# output.net
KiCad netlist of a schematic drawn in Altium Designer
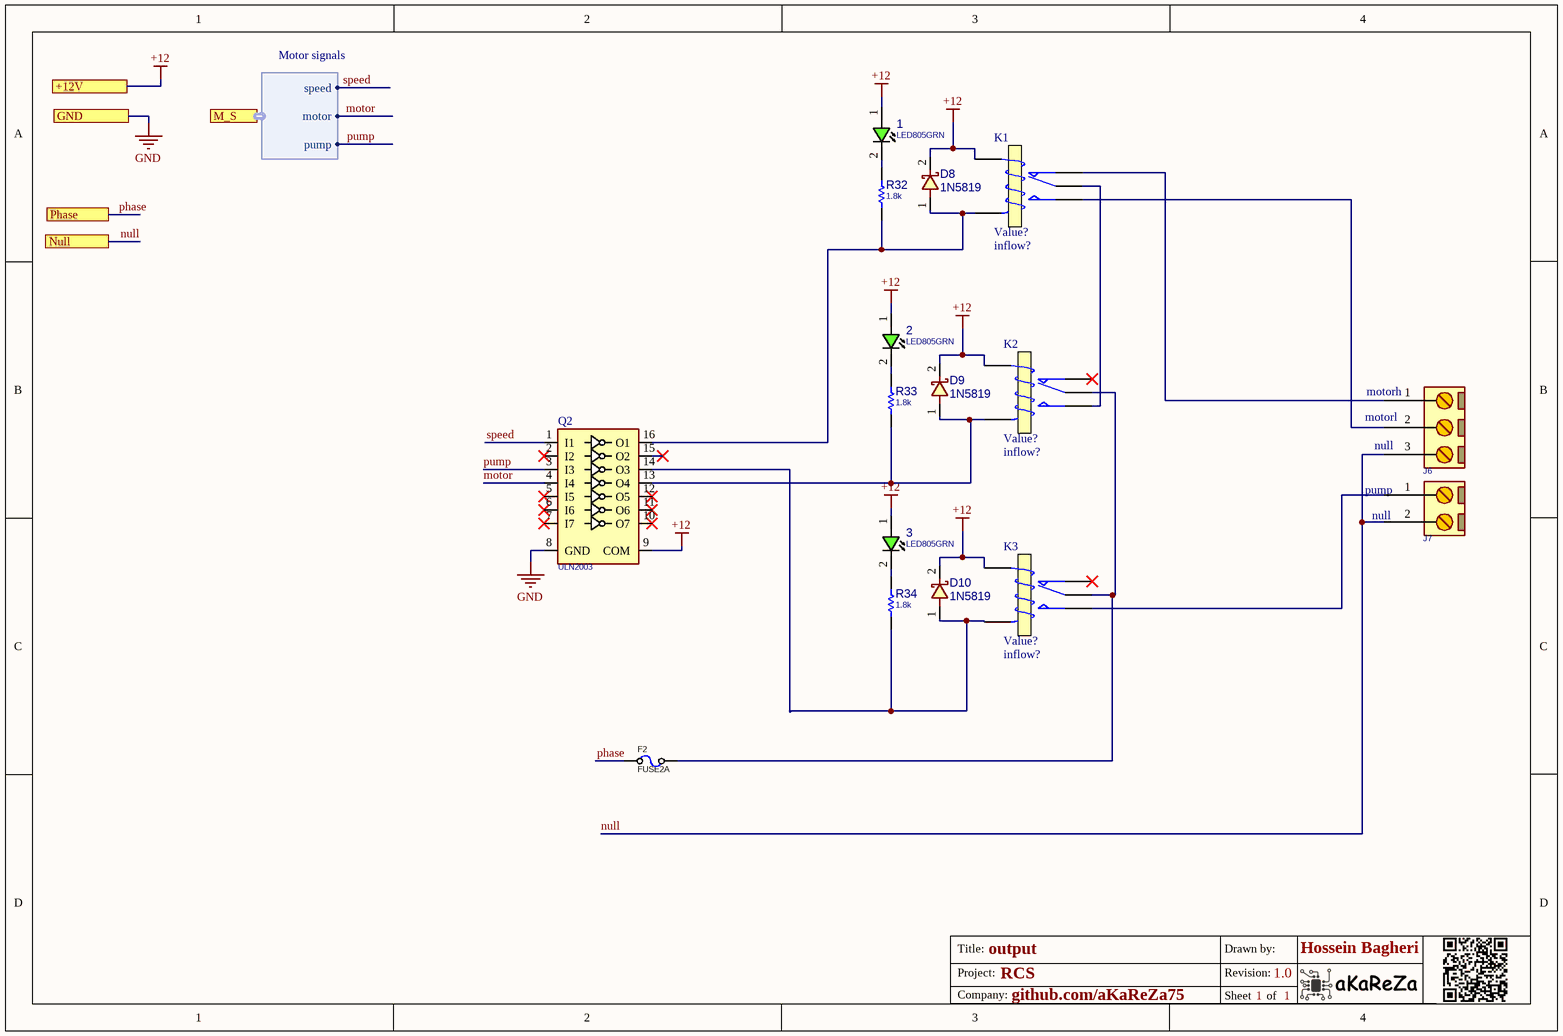
[diagram p0: output.SchDoc]

(export (version "E")
  (design (tool "Eeschema 10.0.6"))
  (components
    (comp (ref "1")
      (value "LED805GRN")
      (footprint "LED0805GRN")
      (description "LED, SMD, 0805, GREEN")
      (libsource (lib "Chila_PCB") (part "LED_SMD_0805_GRN"))
    )
    (comp (ref "2")
      (value "LED805GRN")
      (footprint "LED0805GRN")
      (description "LED, SMD, 0805, GREEN")
      (libsource (lib "Chila_PCB") (part "LED_SMD_0805_GRN"))
    )
    (comp (ref "3")
      (value "LED805GRN")
      (footprint "LED0805GRN")
      (description "LED, SMD, 0805, GREEN")
      (libsource (lib "Chila_PCB") (part "LED_SMD_0805_GRN"))
    )
    (comp (ref "D8")
      (value "1N5819")
      (footprint "D_SOD123W")
      (description "DIODE, SCHOTTKY, 40V, 1A")
      (fields (field (name "MANF") "DIODES") (field (name "MANF_P#") "1N5819HW-7-F"))
      (libsource (lib "Chila_PCB") (part "DIODE_SMD_SCHOTTKY_1N5819"))
    )
    (comp (ref "D9")
      (value "1N5819")
      (footprint "D_SOD123W")
      (description "DIODE, SCHOTTKY, 40V, 1A")
      (fields (field (name "MANF") "DIODES") (field (name "MANF_P#") "1N5819HW-7-F"))
      (libsource (lib "Chila_PCB") (part "DIODE_SMD_SCHOTTKY_1N5819"))
    )
    (comp (ref "D10")
      (value "1N5819")
      (footprint "D_SOD123W")
      (description "DIODE, SCHOTTKY, 40V, 1A")
      (fields (field (name "MANF") "DIODES") (field (name "MANF_P#") "1N5819HW-7-F"))
      (libsource (lib "Chila_PCB") (part "DIODE_SMD_SCHOTTKY_1N5819"))
    )
    (comp (ref "F2")
      (value "FUSE2A")
      (footprint "FUSH_5X20MM")
      (description "Fuse HOLDER 5X20")
      (fields (field (name "MANF") "MANF") (field (name "MANF_P#") "MANF_PART#"))
      (libsource (lib "Chila_PCB") (part "FUSE_5X20"))
    )
    (comp (ref "J6")
      (value "CONN_GMSTB3")
      (footprint "GMSTB762_3")
      (description "CONN, PHOENIX MSTB, 5-G, 5.08mm pitch")
      (fields (field (name "MANF_P#") "GMSTB 2,5/3-G-7,62"))
      (libsource (lib "Chila_PCB") (part "CONN_GMSTB762_3"))
    )
    (comp (ref "J7")
      (value "CONN_GMSTB2")
      (footprint "GMSTB762_2")
      (description "CONN, PHOENIX GMSTB, 7.62mm pitch")
      (fields (field (name "MANF_P#") "GMSTB 2,5/2-G-7,62"))
      (libsource (lib "Chila_PCB") (part "CONN_GMSTB762_2"))
    )
    (comp (ref "K1")
      (value "Value?")
      (footprint "Relay 15.40x12.10x13.10")
      (description "SPDT Relay")
      (fields (field (name "INFLOW") "inflow?") (field (name "VALIDATION") "Valid"))
      (libsource (lib "aKaReZa") (part "SW_Relay_SPDT"))
    )
    (comp (ref "K2")
      (value "Value?")
      (footprint "Relay 15.40x12.10x13.10")
      (description "SPDT Relay")
      (fields (field (name "INFLOW") "inflow?") (field (name "VALIDATION") "Valid"))
      (libsource (lib "aKaReZa") (part "SW_Relay_SPDT"))
    )
    (comp (ref "K3")
      (value "Value?")
      (footprint "Relay 15.40x12.10x13.10")
      (description "SPDT Relay")
      (fields (field (name "INFLOW") "inflow?") (field (name "VALIDATION") "Valid"))
      (libsource (lib "aKaReZa") (part "SW_Relay_SPDT"))
    )
    (comp (ref "Q2")
      (value "ULN2003")
      (footprint "SO_16_W")
      (description "Darlington, 7-CH, 50V, 0.5A")
      (fields (field (name "MANF_P#") "ULN2003A") (field (name "MANF") "DIODES"))
      (libsource (lib "Chila_PCB") (part "ULN2003_SOP16"))
    )
    (comp (ref "R32")
      (value "1.8k")
      (footprint "R0805")
      (description "RESISTOR, SMD")
      (libsource (lib "Chila_PCB") (part "RES_SMD_0805"))
    )
    (comp (ref "R33")
      (value "1.8k")
      (footprint "R0805")
      (description "RESISTOR, SMD")
      (libsource (lib "Chila_PCB") (part "RES_SMD_0805"))
    )
    (comp (ref "R34")
      (value "1.8k")
      (footprint "R0805")
      (description "RESISTOR, SMD")
      (libsource (lib "Chila_PCB") (part "RES_SMD_0805"))
    )
  )
  (nets
    (net (code "3") (name "+12") (class "Default")
      (node (ref "1") (pin "1") (pinfunction "ANODE_1") (pintype "passive"))
      (node (ref "2") (pin "1") (pinfunction "ANODE_1") (pintype "passive"))
      (node (ref "3") (pin "1") (pinfunction "ANODE_1") (pintype "passive"))
      (node (ref "D10") (pin "2") (pinfunction "2_2") (pintype "passive"))
      (node (ref "D8") (pin "2") (pinfunction "2_2") (pintype "passive"))
      (node (ref "D9") (pin "2") (pinfunction "2_2") (pintype "passive"))
      (node (ref "K1") (pin "4") (pinfunction "T1_4") (pintype "passive"))
      (node (ref "K2") (pin "4") (pinfunction "T1_4") (pintype "passive"))
      (node (ref "K3") (pin "4") (pinfunction "T1_4") (pintype "passive"))
      (node (ref "Q2") (pin "9") (pinfunction "COM_9") (pintype "passive"))
    )
    (net (code "4") (name "/motor") (class "Default")
      (node (ref "Q2") (pin "4") (pinfunction "I4_4") (pintype "passive"))
    )
    (net (code "5") (name "/null") (class "Default")
      (node (ref "J6") (pin "3") (pinfunction "3_3") (pintype "passive"))
      (node (ref "J7") (pin "2") (pinfunction "2_2") (pintype "passive"))
    )
    (net (code "6") (name "/phase") (class "Default")
      (node (ref "F2") (pin "1") (pinfunction "1_1") (pintype "passive"))
    )
    (net (code "7") (name "/pump") (class "Default")
      (node (ref "Q2") (pin "3") (pinfunction "I3_3") (pintype "passive"))
    )
    (net (code "8") (name "/speed") (class "Default")
      (node (ref "Q2") (pin "1") (pinfunction "I1_1") (pintype "passive"))
    )
    (net (code "10") (name "GND") (class "Default")
      (node (ref "Q2") (pin "8") (pinfunction "GND_8") (pintype "passive"))
    )
    (net (code "11") (name "Net-(1-CATHODE)") (class "Default")
      (node (ref "1") (pin "2") (pinfunction "CATHODE_2") (pintype "passive"))
      (node (ref "R32") (pin "2") (pinfunction "2_2") (pintype "passive"))
    )
    (net (code "12") (name "Net-(2-CATHODE)") (class "Default")
      (node (ref "2") (pin "2") (pinfunction "CATHODE_2") (pintype "passive"))
      (node (ref "R33") (pin "2") (pinfunction "2_2") (pintype "passive"))
    )
    (net (code "13") (name "Net-(3-CATHODE)") (class "Default")
      (node (ref "3") (pin "2") (pinfunction "CATHODE_2") (pintype "passive"))
      (node (ref "R34") (pin "2") (pinfunction "2_2") (pintype "passive"))
    )
    (net (code "14") (name "Net-(K1-COM)") (class "Default")
      (node (ref "K1") (pin "1") (pinfunction "COM_1") (pintype "passive"))
      (node (ref "K2") (pin "3") (pinfunction "NO_3") (pintype "passive"))
    )
    (net (code "15") (name "Net-(K1-NC)") (class "Default")
      (node (ref "J6") (pin "1") (pinfunction "1_1") (pintype "passive"))
      (node (ref "K1") (pin "2") (pinfunction "NC_2") (pintype "passive"))
    )
    (net (code "16") (name "Net-(K1-NO)") (class "Default")
      (node (ref "J6") (pin "2") (pinfunction "2_2") (pintype "passive"))
      (node (ref "K1") (pin "3") (pinfunction "NO_3") (pintype "passive"))
    )
    (net (code "17") (name "Net-(K1-T2)") (class "Default")
      (node (ref "D8") (pin "1") (pinfunction "1_1") (pintype "passive"))
      (node (ref "K1") (pin "5") (pinfunction "T2_5") (pintype "passive"))
      (node (ref "Q2") (pin "16") (pinfunction "O1_16") (pintype "passive"))
      (node (ref "R32") (pin "1") (pinfunction "1_1") (pintype "passive"))
    )
    (net (code "18") (name "Net-(K2-COM)") (class "Default")
      (node (ref "F2") (pin "2") (pinfunction "2_2") (pintype "passive"))
      (node (ref "K2") (pin "1") (pinfunction "COM_1") (pintype "passive"))
      (node (ref "K3") (pin "1") (pinfunction "COM_1") (pintype "passive"))
    )
    (net (code "19") (name "Net-(K2-T2)") (class "Default")
      (node (ref "D9") (pin "1") (pinfunction "1_1") (pintype "passive"))
      (node (ref "K2") (pin "5") (pinfunction "T2_5") (pintype "passive"))
      (node (ref "Q2") (pin "13") (pinfunction "O4_13") (pintype "passive"))
      (node (ref "R33") (pin "1") (pinfunction "1_1") (pintype "passive"))
    )
    (net (code "20") (name "Net-(K3-NO)") (class "Default")
      (node (ref "J7") (pin "1") (pinfunction "1_1") (pintype "passive"))
      (node (ref "K3") (pin "3") (pinfunction "NO_3") (pintype "passive"))
    )
    (net (code "21") (name "Net-(K3-T2)") (class "Default")
      (node (ref "D10") (pin "1") (pinfunction "1_1") (pintype "passive"))
      (node (ref "K3") (pin "5") (pinfunction "T2_5") (pintype "passive"))
      (node (ref "Q2") (pin "14") (pinfunction "O3_14") (pintype "passive"))
      (node (ref "R34") (pin "1") (pinfunction "1_1") (pintype "passive"))
    )
    (net (code "22") (name "unconnected-(K2-NC-Pad2)") (class "Default")
      (node (ref "K2") (pin "2") (pinfunction "NC_2") (pintype "passive+no_connect"))
    )
    (net (code "23") (name "unconnected-(K3-NC-Pad2)") (class "Default")
      (node (ref "K3") (pin "2") (pinfunction "NC_2") (pintype "passive+no_connect"))
    )
    (net (code "24") (name "unconnected-(Q2-I2-Pad2)") (class "Default")
      (node (ref "Q2") (pin "2") (pinfunction "I2_2") (pintype "passive+no_connect"))
    )
    (net (code "25") (name "unconnected-(Q2-I5-Pad5)") (class "Default")
      (node (ref "Q2") (pin "5") (pinfunction "I5_5") (pintype "passive+no_connect"))
    )
    (net (code "26") (name "unconnected-(Q2-I6-Pad6)") (class "Default")
      (node (ref "Q2") (pin "6") (pinfunction "I6_6") (pintype "passive+no_connect"))
    )
    (net (code "27") (name "unconnected-(Q2-I7-Pad7)") (class "Default")
      (node (ref "Q2") (pin "7") (pinfunction "I7_7") (pintype "passive+no_connect"))
    )
    (net (code "28") (name "unconnected-(Q2-O2-Pad15)") (class "Default")
      (node (ref "Q2") (pin "15") (pinfunction "O2_15") (pintype "passive+no_connect"))
    )
    (net (code "29") (name "unconnected-(Q2-O5-Pad12)") (class "Default")
      (node (ref "Q2") (pin "12") (pinfunction "O5_12") (pintype "passive+no_connect"))
    )
    (net (code "30") (name "unconnected-(Q2-O6-Pad11)") (class "Default")
      (node (ref "Q2") (pin "11") (pinfunction "O6_11") (pintype "passive+no_connect"))
    )
    (net (code "31") (name "unconnected-(Q2-O7-Pad10)") (class "Default")
      (node (ref "Q2") (pin "10") (pinfunction "O7_10") (pintype "passive+no_connect"))
    )
  )
)
